# BodyTempUnit-e7.net
KiCad netlist of a schematic drawn in EAGLE
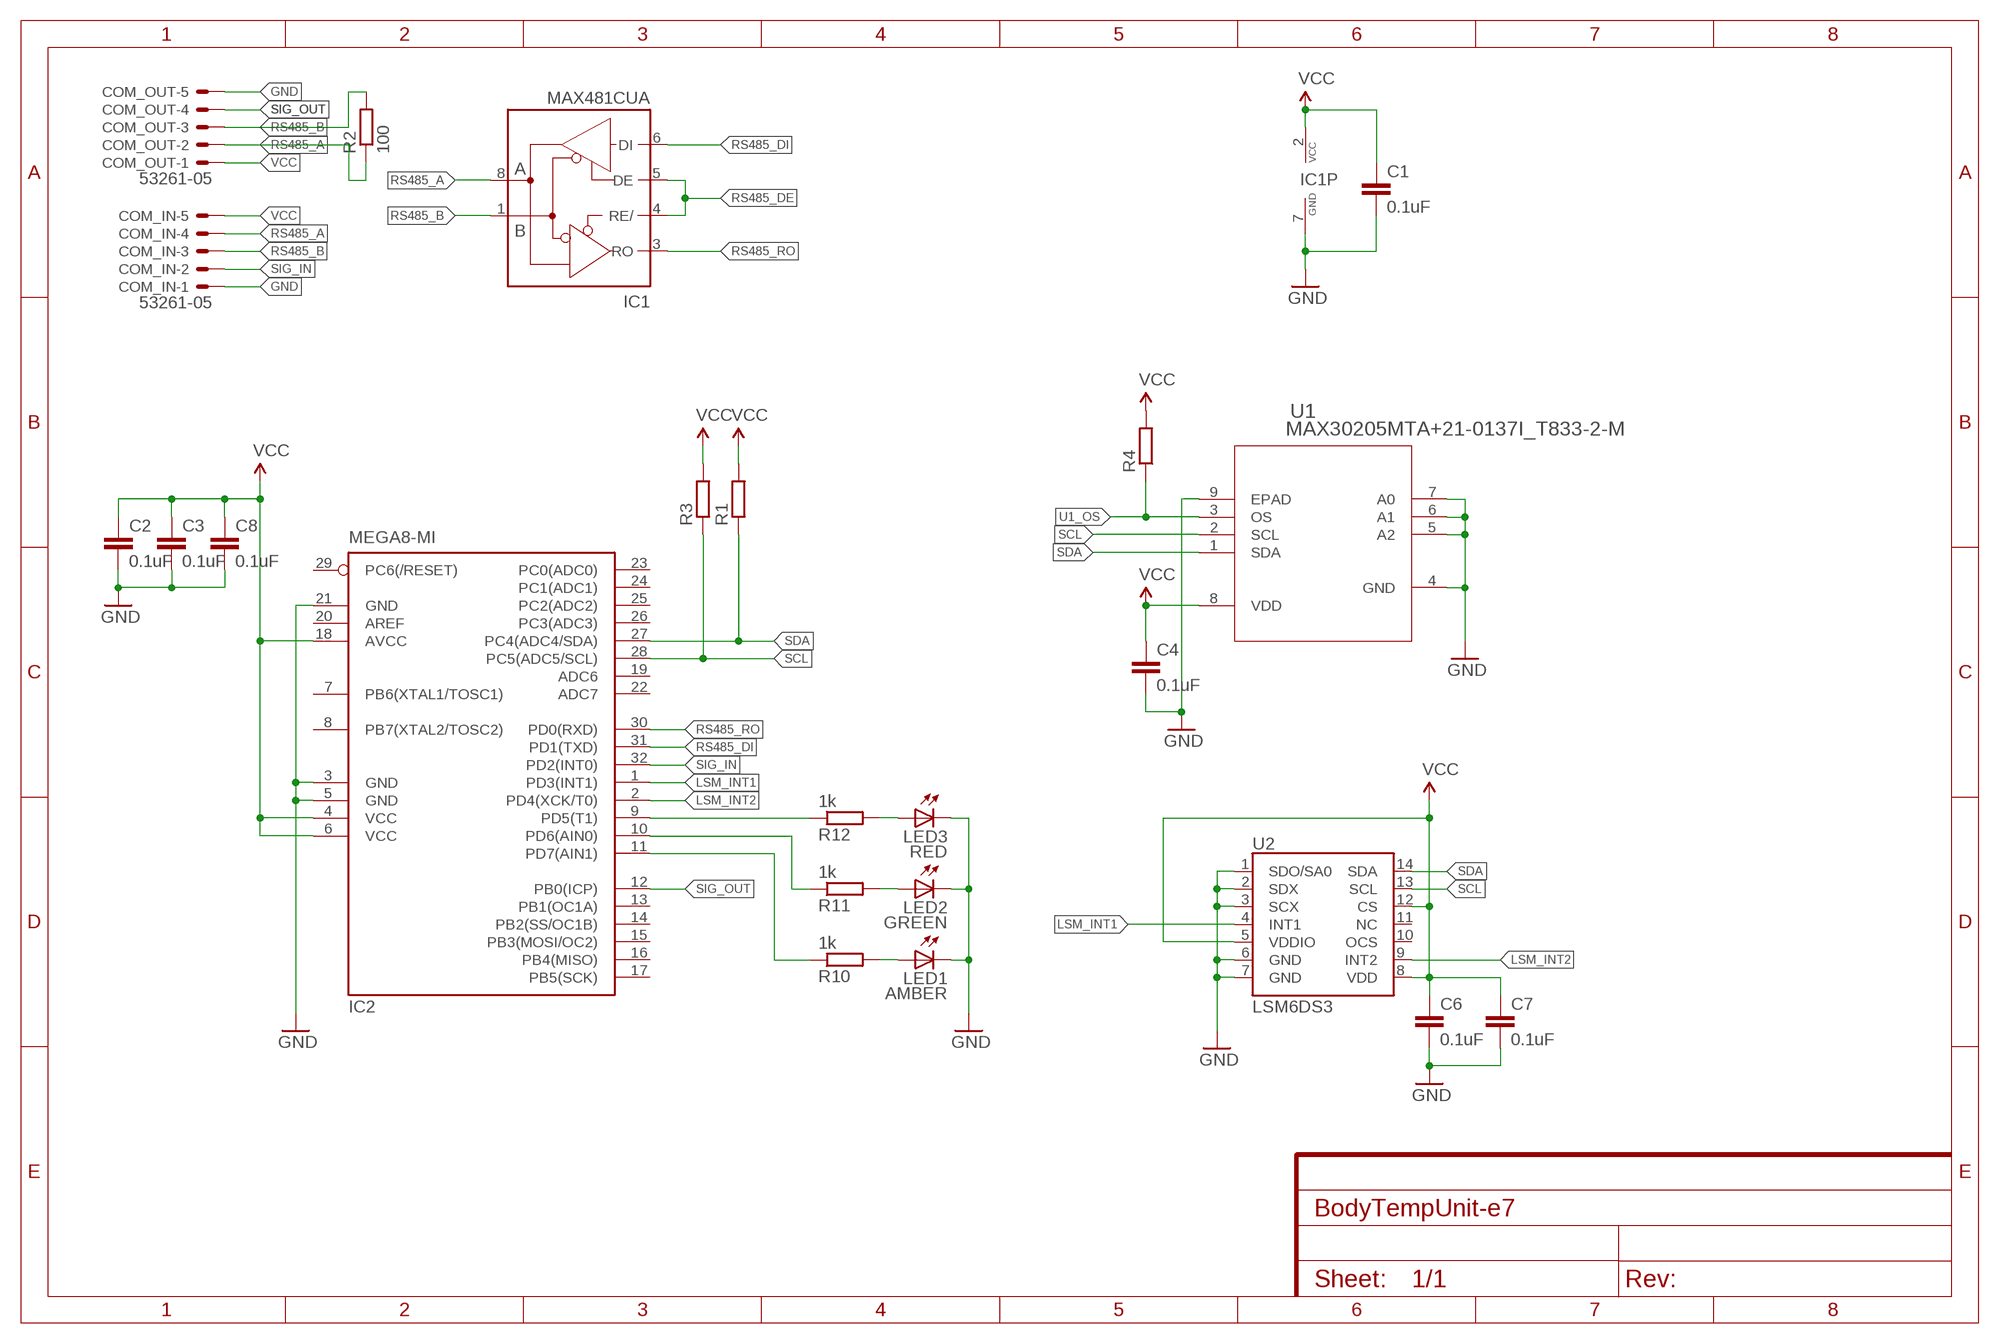
[diagram p0: schematic, sheet 1]

(export (version "E")
  (design (tool "Eeschema 10.0.6"))
  (components
    (comp (ref "C1")
      (value "0.1uF")
      (footprint "eagle-import:C0603K")
      (libsource (lib "eagle-import") (part "C-EUC0603K"))
    )
    (comp (ref "C2")
      (value "0.1uF")
      (footprint "eagle-import:C0603K")
      (libsource (lib "eagle-import") (part "C-EUC0603K"))
    )
    (comp (ref "C3")
      (value "0.1uF")
      (footprint "eagle-import:C0603K")
      (libsource (lib "eagle-import") (part "C-EUC0603K"))
    )
    (comp (ref "C4")
      (value "0.1uF")
      (footprint "eagle-import:C0603K")
      (libsource (lib "eagle-import") (part "C-EUC0603K"))
    )
    (comp (ref "C6")
      (value "0.1uF")
      (footprint "eagle-import:C0603K")
      (libsource (lib "eagle-import") (part "C-EUC0603K"))
    )
    (comp (ref "C7")
      (value "0.1uF")
      (footprint "eagle-import:C0603K")
      (libsource (lib "eagle-import") (part "C-EUC0603K"))
    )
    (comp (ref "C8")
      (value "0.1uF")
      (footprint "eagle-import:C0603K")
      (libsource (lib "eagle-import") (part "C-EUC0603K"))
    )
    (comp (ref "COM_IN")
      (value "53261-05")
      (footprint "eagle-import:53261-05")
      (fields (field (name "MF") "MOLEX"))
      (libsource (lib "eagle-import") (part "53?-05261"))
    )
    (comp (ref "COM_OUT")
      (value "53261-05")
      (footprint "eagle-import:53261-05")
      (fields (field (name "MF") "MOLEX"))
      (libsource (lib "eagle-import") (part "53?-05261"))
    )
    (comp (ref "IC1")
      (value "MAX481CUA")
      (footprint "eagle-import:UMAX8")
      (fields (field (name "MPN") "MAX481CUA+"))
      (libsource (lib "eagle-import") (part "MAX481CUA"))
    )
    (comp (ref "IC2")
      (value "MEGA8-MI")
      (footprint "eagle-import:MLF32")
      (fields (field (name "MPN") "ATMEGA88PA-MU"))
      (libsource (lib "eagle-import") (part "MEGA8-MI"))
    )
    (comp (ref "LED1")
      (value "AMBER")
      (footprint "eagle-import:CHIPLED_0603")
      (libsource (lib "eagle-import") (part "LEDCHIPLED_0603"))
    )
    (comp (ref "LED2")
      (value "GREEN")
      (footprint "eagle-import:CHIPLED_0603")
      (libsource (lib "eagle-import") (part "LEDCHIPLED_0603"))
    )
    (comp (ref "LED3")
      (value "RED")
      (footprint "eagle-import:CHIPLED_0603")
      (libsource (lib "eagle-import") (part "LEDCHIPLED_0603"))
    )
    (comp (ref "R1")
      (value "R-EU_R0603")
      (footprint "eagle-import:R0603")
      (libsource (lib "eagle-import") (part "R-EU_R0603"))
    )
    (comp (ref "R2")
      (value "100")
      (footprint "eagle-import:R0603")
      (libsource (lib "eagle-import") (part "R-EU_R0603"))
    )
    (comp (ref "R3")
      (value "R-EU_R0603")
      (footprint "eagle-import:R0603")
      (libsource (lib "eagle-import") (part "R-EU_R0603"))
    )
    (comp (ref "R4")
      (value "R-EU_R0603")
      (footprint "eagle-import:R0603")
      (libsource (lib "eagle-import") (part "R-EU_R0603"))
    )
    (comp (ref "R10")
      (value "1k")
      (footprint "eagle-import:R0603")
      (libsource (lib "eagle-import") (part "rcl@1_R-EU_R0603"))
    )
    (comp (ref "R11")
      (value "1k")
      (footprint "eagle-import:R0603")
      (libsource (lib "eagle-import") (part "rcl@1_R-EU_R0603"))
    )
    (comp (ref "R12")
      (value "1k")
      (footprint "eagle-import:R0603")
      (libsource (lib "eagle-import") (part "rcl@1_R-EU_R0603"))
    )
    (comp (ref "U1")
      (value "MAX30205MTA+21-0137I_T833-2-M")
      (footprint "eagle-import:21-0137I_T833-2-M")
      (fields (field (name "MANUFACTURER_PART_NUMBER") "MAX30205MTA+"))
      (libsource (lib "eagle-import") (part "MAX30205MTA+21-0137I_T833-2-M"))
    )
    (comp (ref "U2")
      (value "LSM6DS3")
      (footprint "eagle-import:LGA14L")
      (libsource (lib "eagle-import") (part "LSM6DS3"))
    )
  )
  (nets
    (net (code "1") (name "GND") (class "Default")
      (node (ref "C1") (pin "2") (pinfunction "2_2") (pintype "passive"))
      (node (ref "C2") (pin "2") (pinfunction "2_2") (pintype "passive"))
      (node (ref "C3") (pin "2") (pinfunction "2_2") (pintype "passive"))
      (node (ref "C4") (pin "2") (pinfunction "2_2") (pintype "passive"))
      (node (ref "C6") (pin "2") (pinfunction "2_2") (pintype "passive"))
      (node (ref "C7") (pin "2") (pinfunction "2_2") (pintype "passive"))
      (node (ref "C8") (pin "2") (pinfunction "2_2") (pintype "passive"))
      (node (ref "COM_IN") (pin "1") (pinfunction "S_1") (pintype "passive"))
      (node (ref "COM_OUT") (pin "5") (pinfunction "S_5") (pintype "passive"))
      (node (ref "IC1") (pin "7") (pinfunction "GND_7") (pintype "power_in"))
      (node (ref "IC2") (pin "21") (pinfunction "GND_21") (pintype "power_in"))
      (node (ref "IC2") (pin "3") (pinfunction "GND_3") (pintype "power_in"))
      (node (ref "IC2") (pin "5") (pinfunction "GND_5") (pintype "power_in"))
      (node (ref "LED1") (pin "C") (pinfunction "C_C") (pintype "passive"))
      (node (ref "LED2") (pin "C") (pinfunction "C_C") (pintype "passive"))
      (node (ref "LED3") (pin "C") (pinfunction "C_C") (pintype "passive"))
      (node (ref "U1") (pin "4") (pinfunction "GND_4") (pintype "passive"))
      (node (ref "U1") (pin "5") (pinfunction "A2_5") (pintype "bidirectional"))
      (node (ref "U1") (pin "6") (pinfunction "A1_6") (pintype "bidirectional"))
      (node (ref "U1") (pin "7") (pinfunction "A0_7") (pintype "bidirectional"))
      (node (ref "U1") (pin "9") (pinfunction "EPAD_9") (pintype "passive"))
      (node (ref "U2") (pin "1") (pinfunction "SDO/SA0_1") (pintype "bidirectional"))
      (node (ref "U2") (pin "2") (pinfunction "SDX_2") (pintype "bidirectional"))
      (node (ref "U2") (pin "3") (pinfunction "SCX_3") (pintype "bidirectional"))
      (node (ref "U2") (pin "6") (pinfunction "GND_6") (pintype "bidirectional"))
      (node (ref "U2") (pin "7") (pinfunction "GND_7") (pintype "bidirectional"))
    )
    (net (code "2") (name "LSM_INT1") (class "Default")
      (node (ref "IC2") (pin "1") (pinfunction "PD3(INT1)_1") (pintype "bidirectional"))
      (node (ref "U2") (pin "4") (pinfunction "INT1_4") (pintype "bidirectional"))
    )
    (net (code "3") (name "LSM_INT2") (class "Default")
      (node (ref "IC2") (pin "2") (pinfunction "PD4(XCK/T0)_2") (pintype "bidirectional"))
      (node (ref "U2") (pin "9") (pinfunction "INT2_9") (pintype "bidirectional"))
    )
    (net (code "4") (name "Net-(IC2-PD5(T1))") (class "Default")
      (node (ref "IC2") (pin "9") (pinfunction "PD5(T1)_9") (pintype "bidirectional"))
      (node (ref "R12") (pin "1") (pinfunction "1_1") (pintype "passive"))
    )
    (net (code "5") (name "Net-(IC2-PD6(AIN0))") (class "Default")
      (node (ref "IC2") (pin "10") (pinfunction "PD6(AIN0)_10") (pintype "bidirectional"))
      (node (ref "R11") (pin "1") (pinfunction "1_1") (pintype "passive"))
    )
    (net (code "6") (name "Net-(IC2-PD7(AIN1))") (class "Default")
      (node (ref "IC2") (pin "11") (pinfunction "PD7(AIN1)_11") (pintype "bidirectional"))
      (node (ref "R10") (pin "1") (pinfunction "1_1") (pintype "passive"))
    )
    (net (code "7") (name "Net-(LED1-PadA)") (class "Default")
      (node (ref "LED1") (pin "A") (pinfunction "A_A") (pintype "passive"))
      (node (ref "R10") (pin "2") (pinfunction "2_2") (pintype "passive"))
    )
    (net (code "8") (name "Net-(LED2-PadA)") (class "Default")
      (node (ref "LED2") (pin "A") (pinfunction "A_A") (pintype "passive"))
      (node (ref "R11") (pin "2") (pinfunction "2_2") (pintype "passive"))
    )
    (net (code "9") (name "Net-(LED3-PadA)") (class "Default")
      (node (ref "LED3") (pin "A") (pinfunction "A_A") (pintype "passive"))
      (node (ref "R12") (pin "2") (pinfunction "2_2") (pintype "passive"))
    )
    (net (code "10") (name "RS485_A") (class "Default")
      (node (ref "COM_IN") (pin "4") (pinfunction "S_4") (pintype "passive"))
      (node (ref "COM_OUT") (pin "2") (pinfunction "S_2") (pintype "passive"))
      (node (ref "IC1") (pin "8") (pinfunction "A_8") (pintype "passive"))
      (node (ref "R2") (pin "1") (pinfunction "1_1") (pintype "passive"))
    )
    (net (code "11") (name "RS485_B") (class "Default")
      (node (ref "COM_IN") (pin "3") (pinfunction "S_3") (pintype "passive"))
      (node (ref "COM_OUT") (pin "3") (pinfunction "S_3") (pintype "passive"))
      (node (ref "IC1") (pin "1") (pinfunction "B_1") (pintype "passive"))
      (node (ref "R2") (pin "2") (pinfunction "2_2") (pintype "passive"))
    )
    (net (code "12") (name "RS485_DE") (class "Default")
      (node (ref "IC1") (pin "4") (pinfunction "RE/_4") (pintype "input"))
      (node (ref "IC1") (pin "5") (pinfunction "DE_5") (pintype "input"))
    )
    (net (code "13") (name "RS485_DI") (class "Default")
      (node (ref "IC1") (pin "6") (pinfunction "DI_6") (pintype "input"))
      (node (ref "IC2") (pin "31") (pinfunction "PD1(TXD)_31") (pintype "bidirectional"))
    )
    (net (code "14") (name "RS485_RO") (class "Default")
      (node (ref "IC1") (pin "3") (pinfunction "RO_3") (pintype "output"))
      (node (ref "IC2") (pin "30") (pinfunction "PD0(RXD)_30") (pintype "bidirectional"))
    )
    (net (code "15") (name "SCL") (class "Default")
      (node (ref "IC2") (pin "28") (pinfunction "PC5(ADC5/SCL)_28") (pintype "bidirectional"))
      (node (ref "R3") (pin "1") (pinfunction "1_1") (pintype "passive"))
      (node (ref "U1") (pin "2") (pinfunction "SCL_2") (pintype "passive"))
      (node (ref "U2") (pin "13") (pinfunction "SCL_13") (pintype "bidirectional"))
    )
    (net (code "16") (name "SDA") (class "Default")
      (node (ref "IC2") (pin "27") (pinfunction "PC4(ADC4/SDA)_27") (pintype "bidirectional"))
      (node (ref "R1") (pin "1") (pinfunction "1_1") (pintype "passive"))
      (node (ref "U1") (pin "1") (pinfunction "SDA_1") (pintype "passive"))
      (node (ref "U2") (pin "14") (pinfunction "SDA_14") (pintype "bidirectional"))
    )
    (net (code "17") (name "SIG_IN") (class "Default")
      (node (ref "COM_IN") (pin "2") (pinfunction "S_2") (pintype "passive"))
      (node (ref "IC2") (pin "32") (pinfunction "PD2(INT0)_32") (pintype "bidirectional"))
    )
    (net (code "18") (name "SIG_OUT") (class "Default")
      (node (ref "COM_OUT") (pin "4") (pinfunction "S_4") (pintype "passive"))
      (node (ref "IC2") (pin "12") (pinfunction "PB0(ICP)_12") (pintype "bidirectional"))
    )
    (net (code "19") (name "U1_OS") (class "Default")
      (node (ref "R4") (pin "1") (pinfunction "1_1") (pintype "passive"))
      (node (ref "U1") (pin "3") (pinfunction "OS_3") (pintype "passive"))
    )
    (net (code "20") (name "VCC") (class "Default")
      (node (ref "C1") (pin "1") (pinfunction "1_1") (pintype "passive"))
      (node (ref "C2") (pin "1") (pinfunction "1_1") (pintype "passive"))
      (node (ref "C3") (pin "1") (pinfunction "1_1") (pintype "passive"))
      (node (ref "C4") (pin "1") (pinfunction "1_1") (pintype "passive"))
      (node (ref "C6") (pin "1") (pinfunction "1_1") (pintype "passive"))
      (node (ref "C7") (pin "1") (pinfunction "1_1") (pintype "passive"))
      (node (ref "C8") (pin "1") (pinfunction "1_1") (pintype "passive"))
      (node (ref "COM_IN") (pin "5") (pinfunction "S_5") (pintype "passive"))
      (node (ref "COM_OUT") (pin "1") (pinfunction "S_1") (pintype "passive"))
      (node (ref "IC1") (pin "2") (pinfunction "VCC_2") (pintype "power_in"))
      (node (ref "IC2") (pin "18") (pinfunction "AVCC_18") (pintype "power_in"))
      (node (ref "IC2") (pin "4") (pinfunction "VCC_4") (pintype "power_in"))
      (node (ref "IC2") (pin "6") (pinfunction "VCC_6") (pintype "power_in"))
      (node (ref "R1") (pin "2") (pinfunction "2_2") (pintype "passive"))
      (node (ref "R3") (pin "2") (pinfunction "2_2") (pintype "passive"))
      (node (ref "R4") (pin "2") (pinfunction "2_2") (pintype "passive"))
      (node (ref "U1") (pin "8") (pinfunction "VDD_8") (pintype "power_in"))
      (node (ref "U2") (pin "12") (pinfunction "CS_12") (pintype "bidirectional"))
      (node (ref "U2") (pin "5") (pinfunction "VDDIO_5") (pintype "bidirectional"))
      (node (ref "U2") (pin "8") (pinfunction "VDD_8") (pintype "bidirectional"))
    )
    (net (code "21") (name "unconnected-(IC2-ADC6-Pad19)") (class "Default")
      (node (ref "IC2") (pin "19") (pinfunction "ADC6_19") (pintype "bidirectional"))
    )
    (net (code "22") (name "unconnected-(IC2-ADC7-Pad22)") (class "Default")
      (node (ref "IC2") (pin "22") (pinfunction "ADC7_22") (pintype "bidirectional"))
    )
    (net (code "23") (name "unconnected-(IC2-AREF-Pad20)") (class "Default")
      (node (ref "IC2") (pin "20") (pinfunction "AREF_20") (pintype "passive"))
    )
    (net (code "24") (name "unconnected-(IC2-PB1(OC1A)-Pad13)") (class "Default")
      (node (ref "IC2") (pin "13") (pinfunction "PB1(OC1A)_13") (pintype "bidirectional"))
    )
    (net (code "25") (name "unconnected-(IC2-PB2(SS{slash}OC1B)-Pad14)") (class "Default")
      (node (ref "IC2") (pin "14") (pinfunction "PB2(SS/OC1B)_14") (pintype "bidirectional"))
    )
    (net (code "26") (name "unconnected-(IC2-PB3(MOSI{slash}OC2)-Pad15)") (class "Default")
      (node (ref "IC2") (pin "15") (pinfunction "PB3(MOSI/OC2)_15") (pintype "bidirectional"))
    )
    (net (code "27") (name "unconnected-(IC2-PB4(MISO)-Pad16)") (class "Default")
      (node (ref "IC2") (pin "16") (pinfunction "PB4(MISO)_16") (pintype "bidirectional"))
    )
    (net (code "28") (name "unconnected-(IC2-PB5(SCK)-Pad17)") (class "Default")
      (node (ref "IC2") (pin "17") (pinfunction "PB5(SCK)_17") (pintype "bidirectional"))
    )
    (net (code "29") (name "unconnected-(IC2-PB6(XTAL1{slash}TOSC1)-Pad7)") (class "Default")
      (node (ref "IC2") (pin "7") (pinfunction "PB6(XTAL1/TOSC1)_7") (pintype "bidirectional"))
    )
    (net (code "30") (name "unconnected-(IC2-PB7(XTAL2{slash}TOSC2)-Pad8)") (class "Default")
      (node (ref "IC2") (pin "8") (pinfunction "PB7(XTAL2/TOSC2)_8") (pintype "bidirectional"))
    )
    (net (code "31") (name "unconnected-(IC2-PC0(ADC0)-Pad23)") (class "Default")
      (node (ref "IC2") (pin "23") (pinfunction "PC0(ADC0)_23") (pintype "bidirectional"))
    )
    (net (code "32") (name "unconnected-(IC2-PC1(ADC1)-Pad24)") (class "Default")
      (node (ref "IC2") (pin "24") (pinfunction "PC1(ADC1)_24") (pintype "bidirectional"))
    )
    (net (code "33") (name "unconnected-(IC2-PC2(ADC2)-Pad25)") (class "Default")
      (node (ref "IC2") (pin "25") (pinfunction "PC2(ADC2)_25") (pintype "bidirectional"))
    )
    (net (code "34") (name "unconnected-(IC2-PC3(ADC3)-Pad26)") (class "Default")
      (node (ref "IC2") (pin "26") (pinfunction "PC3(ADC3)_26") (pintype "bidirectional"))
    )
    (net (code "35") (name "unconnected-(IC2-PC6({slash}RESET)-Pad29)") (class "Default")
      (node (ref "IC2") (pin "29") (pinfunction "PC6(/RESET)_29") (pintype "bidirectional"))
    )
    (net (code "36") (name "unconnected-(U2-NC-Pad11)") (class "Default")
      (node (ref "U2") (pin "11") (pinfunction "NC_11") (pintype "bidirectional"))
    )
    (net (code "37") (name "unconnected-(U2-OCS-Pad10)") (class "Default")
      (node (ref "U2") (pin "10") (pinfunction "OCS_10") (pintype "bidirectional"))
    )
  )
)
